# LED_1.net
KiCad netlist of a schematic drawn in Altium Designer
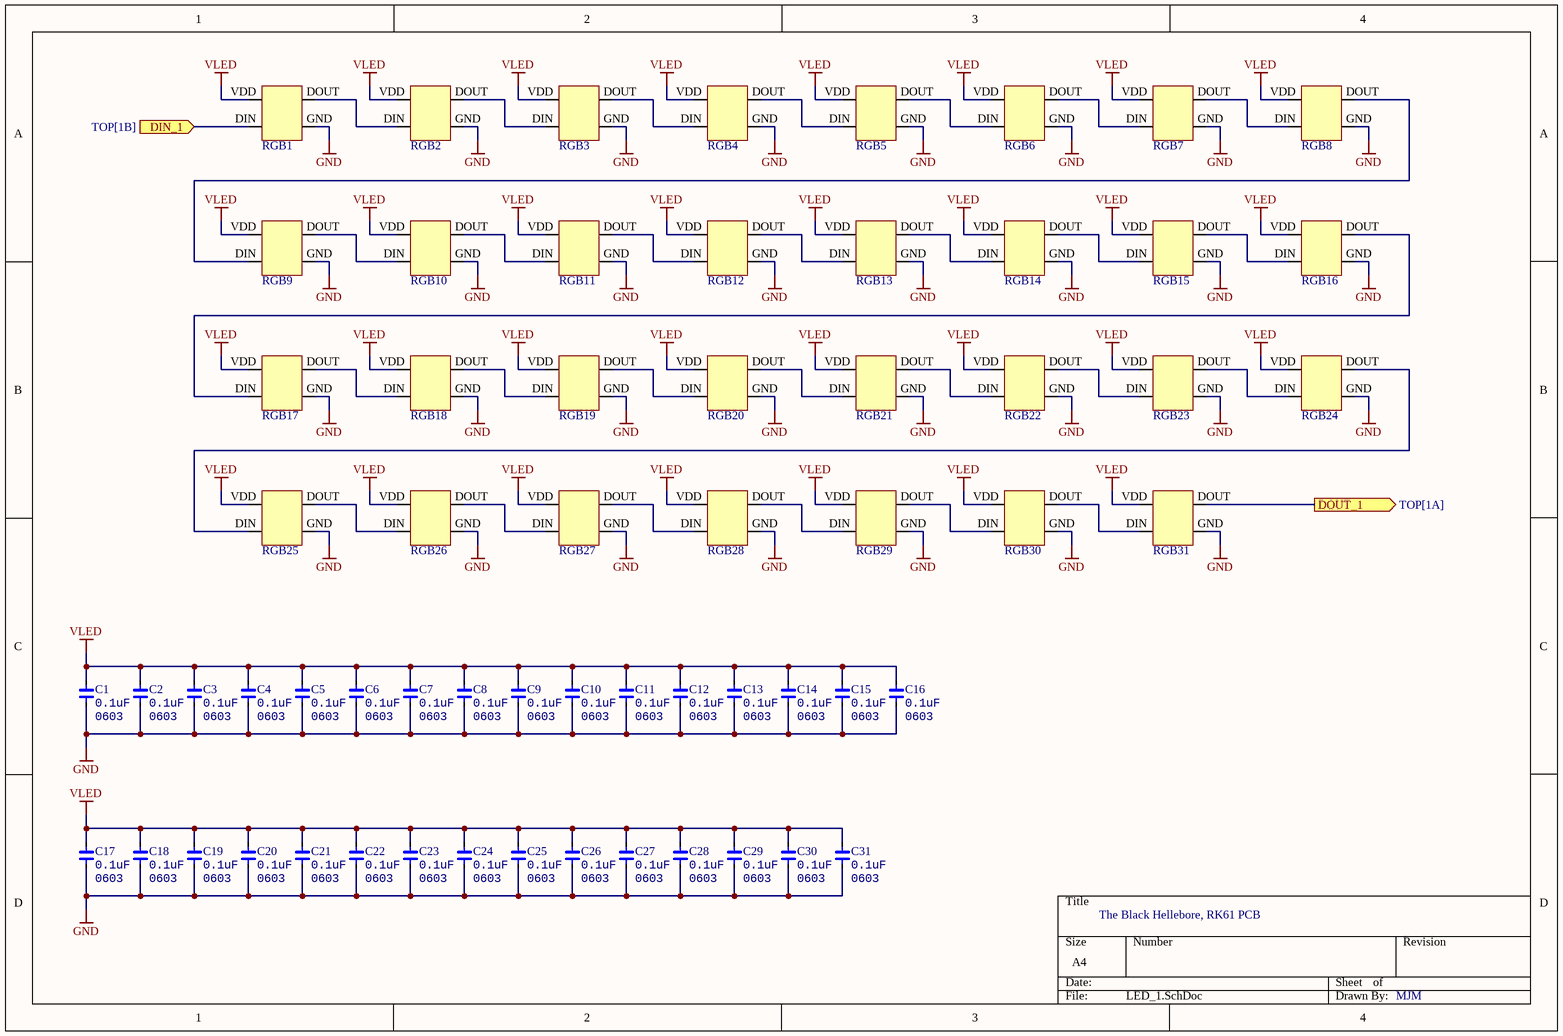
[diagram p0: LED_1.SchDoc]

(export (version "E")
  (design (tool "Eeschema 10.0.6"))
  (components
    (comp (ref "C1")
      (value "0.1uF")
      (footprint "FP-CC0603-DA-MFG")
      (description "0603 0.1 uF 50 V ±5 % Tolerance X7R SMT Multilayer Ceramic Capacitor")
      (fields (field (name "TYPE") "0603") (field (name "Comment") "CC0603JRX7R9BB104"))
      (libsource (lib "Microcom Corporation") (part "M_Cap"))
    )
    (comp (ref "C2")
      (value "0.1uF")
      (footprint "FP-CC0603-DA-MFG")
      (description "0603 0.1 uF 50 V ±5 % Tolerance X7R SMT Multilayer Ceramic Capacitor")
      (fields (field (name "TYPE") "0603") (field (name "Comment") "CC0603JRX7R9BB104"))
      (libsource (lib "Microcom Corporation") (part "M_Cap"))
    )
    (comp (ref "C3")
      (value "0.1uF")
      (footprint "FP-CC0603-DA-MFG")
      (description "0603 0.1 uF 50 V ±5 % Tolerance X7R SMT Multilayer Ceramic Capacitor")
      (fields (field (name "TYPE") "0603") (field (name "Comment") "CC0603JRX7R9BB104"))
      (libsource (lib "Microcom Corporation") (part "M_Cap"))
    )
    (comp (ref "C4")
      (value "0.1uF")
      (footprint "FP-CC0603-DA-MFG")
      (description "0603 0.1 uF 50 V ±5 % Tolerance X7R SMT Multilayer Ceramic Capacitor")
      (fields (field (name "TYPE") "0603") (field (name "Comment") "CC0603JRX7R9BB104"))
      (libsource (lib "Microcom Corporation") (part "M_Cap"))
    )
    (comp (ref "C5")
      (value "0.1uF")
      (footprint "FP-CC0603-DA-MFG")
      (description "0603 0.1 uF 50 V ±5 % Tolerance X7R SMT Multilayer Ceramic Capacitor")
      (fields (field (name "TYPE") "0603") (field (name "Comment") "CC0603JRX7R9BB104"))
      (libsource (lib "Microcom Corporation") (part "M_Cap"))
    )
    (comp (ref "C6")
      (value "0.1uF")
      (footprint "FP-CC0603-DA-MFG")
      (description "0603 0.1 uF 50 V ±5 % Tolerance X7R SMT Multilayer Ceramic Capacitor")
      (fields (field (name "TYPE") "0603") (field (name "Comment") "CC0603JRX7R9BB104"))
      (libsource (lib "Microcom Corporation") (part "M_Cap"))
    )
    (comp (ref "C7")
      (value "0.1uF")
      (footprint "FP-CC0603-DA-MFG")
      (description "0603 0.1 uF 50 V ±5 % Tolerance X7R SMT Multilayer Ceramic Capacitor")
      (fields (field (name "TYPE") "0603") (field (name "Comment") "CC0603JRX7R9BB104"))
      (libsource (lib "Microcom Corporation") (part "M_Cap"))
    )
    (comp (ref "C8")
      (value "0.1uF")
      (footprint "FP-CC0603-DA-MFG")
      (description "0603 0.1 uF 50 V ±5 % Tolerance X7R SMT Multilayer Ceramic Capacitor")
      (fields (field (name "TYPE") "0603") (field (name "Comment") "CC0603JRX7R9BB104"))
      (libsource (lib "Microcom Corporation") (part "M_Cap"))
    )
    (comp (ref "C9")
      (value "0.1uF")
      (footprint "FP-CC0603-DA-MFG")
      (description "0603 0.1 uF 50 V ±5 % Tolerance X7R SMT Multilayer Ceramic Capacitor")
      (fields (field (name "TYPE") "0603") (field (name "Comment") "CC0603JRX7R9BB104"))
      (libsource (lib "Microcom Corporation") (part "M_Cap"))
    )
    (comp (ref "C10")
      (value "0.1uF")
      (footprint "FP-CC0603-DA-MFG")
      (description "0603 0.1 uF 50 V ±5 % Tolerance X7R SMT Multilayer Ceramic Capacitor")
      (fields (field (name "TYPE") "0603") (field (name "Comment") "CC0603JRX7R9BB104"))
      (libsource (lib "Microcom Corporation") (part "M_Cap"))
    )
    (comp (ref "C11")
      (value "0.1uF")
      (footprint "FP-CC0603-DA-MFG")
      (description "0603 0.1 uF 50 V ±5 % Tolerance X7R SMT Multilayer Ceramic Capacitor")
      (fields (field (name "TYPE") "0603") (field (name "Comment") "CC0603JRX7R9BB104"))
      (libsource (lib "Microcom Corporation") (part "M_Cap"))
    )
    (comp (ref "C12")
      (value "0.1uF")
      (footprint "FP-CC0603-DA-MFG")
      (description "0603 0.1 uF 50 V ±5 % Tolerance X7R SMT Multilayer Ceramic Capacitor")
      (fields (field (name "TYPE") "0603") (field (name "Comment") "CC0603JRX7R9BB104"))
      (libsource (lib "Microcom Corporation") (part "M_Cap"))
    )
    (comp (ref "C13")
      (value "0.1uF")
      (footprint "FP-CC0603-DA-MFG")
      (description "0603 0.1 uF 50 V ±5 % Tolerance X7R SMT Multilayer Ceramic Capacitor")
      (fields (field (name "TYPE") "0603") (field (name "Comment") "CC0603JRX7R9BB104"))
      (libsource (lib "Microcom Corporation") (part "M_Cap"))
    )
    (comp (ref "C14")
      (value "0.1uF")
      (footprint "FP-CC0603-DA-MFG")
      (description "0603 0.1 uF 50 V ±5 % Tolerance X7R SMT Multilayer Ceramic Capacitor")
      (fields (field (name "TYPE") "0603") (field (name "Comment") "CC0603JRX7R9BB104"))
      (libsource (lib "Microcom Corporation") (part "M_Cap"))
    )
    (comp (ref "C15")
      (value "0.1uF")
      (footprint "FP-CC0603-DA-MFG")
      (description "0603 0.1 uF 50 V ±5 % Tolerance X7R SMT Multilayer Ceramic Capacitor")
      (fields (field (name "TYPE") "0603") (field (name "Comment") "CC0603JRX7R9BB104"))
      (libsource (lib "Microcom Corporation") (part "M_Cap"))
    )
    (comp (ref "C16")
      (value "0.1uF")
      (footprint "FP-CC0603-DA-MFG")
      (description "0603 0.1 uF 50 V ±5 % Tolerance X7R SMT Multilayer Ceramic Capacitor")
      (fields (field (name "TYPE") "0603") (field (name "Comment") "CC0603JRX7R9BB104"))
      (libsource (lib "Microcom Corporation") (part "M_Cap"))
    )
    (comp (ref "C17")
      (value "0.1uF")
      (footprint "FP-CC0603-DA-MFG")
      (description "0603 0.1 uF 50 V ±5 % Tolerance X7R SMT Multilayer Ceramic Capacitor")
      (fields (field (name "TYPE") "0603") (field (name "Comment") "CC0603JRX7R9BB104"))
      (libsource (lib "Microcom Corporation") (part "M_Cap"))
    )
    (comp (ref "C18")
      (value "0.1uF")
      (footprint "FP-CC0603-DA-MFG")
      (description "0603 0.1 uF 50 V ±5 % Tolerance X7R SMT Multilayer Ceramic Capacitor")
      (fields (field (name "TYPE") "0603") (field (name "Comment") "CC0603JRX7R9BB104"))
      (libsource (lib "Microcom Corporation") (part "M_Cap"))
    )
    (comp (ref "C19")
      (value "0.1uF")
      (footprint "FP-CC0603-DA-MFG")
      (description "0603 0.1 uF 50 V ±5 % Tolerance X7R SMT Multilayer Ceramic Capacitor")
      (fields (field (name "TYPE") "0603") (field (name "Comment") "CC0603JRX7R9BB104"))
      (libsource (lib "Microcom Corporation") (part "M_Cap"))
    )
    (comp (ref "C20")
      (value "0.1uF")
      (footprint "FP-CC0603-DA-MFG")
      (description "0603 0.1 uF 50 V ±5 % Tolerance X7R SMT Multilayer Ceramic Capacitor")
      (fields (field (name "TYPE") "0603") (field (name "Comment") "CC0603JRX7R9BB104"))
      (libsource (lib "Microcom Corporation") (part "M_Cap"))
    )
    (comp (ref "C21")
      (value "0.1uF")
      (footprint "FP-CC0603-DA-MFG")
      (description "0603 0.1 uF 50 V ±5 % Tolerance X7R SMT Multilayer Ceramic Capacitor")
      (fields (field (name "TYPE") "0603") (field (name "Comment") "CC0603JRX7R9BB104"))
      (libsource (lib "Microcom Corporation") (part "M_Cap"))
    )
    (comp (ref "C22")
      (value "0.1uF")
      (footprint "FP-CC0603-DA-MFG")
      (description "0603 0.1 uF 50 V ±5 % Tolerance X7R SMT Multilayer Ceramic Capacitor")
      (fields (field (name "TYPE") "0603") (field (name "Comment") "CC0603JRX7R9BB104"))
      (libsource (lib "Microcom Corporation") (part "M_Cap"))
    )
    (comp (ref "C23")
      (value "0.1uF")
      (footprint "FP-CC0603-DA-MFG")
      (description "0603 0.1 uF 50 V ±5 % Tolerance X7R SMT Multilayer Ceramic Capacitor")
      (fields (field (name "TYPE") "0603") (field (name "Comment") "CC0603JRX7R9BB104"))
      (libsource (lib "Microcom Corporation") (part "M_Cap"))
    )
    (comp (ref "C24")
      (value "0.1uF")
      (footprint "FP-CC0603-DA-MFG")
      (description "0603 0.1 uF 50 V ±5 % Tolerance X7R SMT Multilayer Ceramic Capacitor")
      (fields (field (name "TYPE") "0603") (field (name "Comment") "CC0603JRX7R9BB104"))
      (libsource (lib "Microcom Corporation") (part "M_Cap"))
    )
    (comp (ref "C25")
      (value "0.1uF")
      (footprint "FP-CC0603-DA-MFG")
      (description "0603 0.1 uF 50 V ±5 % Tolerance X7R SMT Multilayer Ceramic Capacitor")
      (fields (field (name "TYPE") "0603") (field (name "Comment") "CC0603JRX7R9BB104"))
      (libsource (lib "Microcom Corporation") (part "M_Cap"))
    )
    (comp (ref "C26")
      (value "0.1uF")
      (footprint "FP-CC0603-DA-MFG")
      (description "0603 0.1 uF 50 V ±5 % Tolerance X7R SMT Multilayer Ceramic Capacitor")
      (fields (field (name "TYPE") "0603") (field (name "Comment") "CC0603JRX7R9BB104"))
      (libsource (lib "Microcom Corporation") (part "M_Cap"))
    )
    (comp (ref "C27")
      (value "0.1uF")
      (footprint "FP-CC0603-DA-MFG")
      (description "0603 0.1 uF 50 V ±5 % Tolerance X7R SMT Multilayer Ceramic Capacitor")
      (fields (field (name "TYPE") "0603") (field (name "Comment") "CC0603JRX7R9BB104"))
      (libsource (lib "Microcom Corporation") (part "M_Cap"))
    )
    (comp (ref "C28")
      (value "0.1uF")
      (footprint "FP-CC0603-DA-MFG")
      (description "0603 0.1 uF 50 V ±5 % Tolerance X7R SMT Multilayer Ceramic Capacitor")
      (fields (field (name "TYPE") "0603") (field (name "Comment") "CC0603JRX7R9BB104"))
      (libsource (lib "Microcom Corporation") (part "M_Cap"))
    )
    (comp (ref "C29")
      (value "0.1uF")
      (footprint "FP-CC0603-DA-MFG")
      (description "0603 0.1 uF 50 V ±5 % Tolerance X7R SMT Multilayer Ceramic Capacitor")
      (fields (field (name "TYPE") "0603") (field (name "Comment") "CC0603JRX7R9BB104"))
      (libsource (lib "Microcom Corporation") (part "M_Cap"))
    )
    (comp (ref "C30")
      (value "0.1uF")
      (footprint "FP-CC0603-DA-MFG")
      (description "0603 0.1 uF 50 V ±5 % Tolerance X7R SMT Multilayer Ceramic Capacitor")
      (fields (field (name "TYPE") "0603") (field (name "Comment") "CC0603JRX7R9BB104"))
      (libsource (lib "Microcom Corporation") (part "M_Cap"))
    )
    (comp (ref "C31")
      (value "0.1uF")
      (footprint "FP-CC0603-DA-MFG")
      (description "0603 0.1 uF 50 V ±5 % Tolerance X7R SMT Multilayer Ceramic Capacitor")
      (fields (field (name "TYPE") "0603") (field (name "Comment") "CC0603JRX7R9BB104"))
      (libsource (lib "Microcom Corporation") (part "M_Cap"))
    )
    (comp (ref "RGB1")
      (value "SK6812MINI-E")
      (footprint "sk6812minie")
      (description "RGB LED SK6812MINI-E")
      (libsource (lib "Microcom Corporation") (part "SK6812MINI-E"))
    )
    (comp (ref "RGB2")
      (value "SK6812MINI-E")
      (footprint "sk6812minie")
      (description "RGB LED SK6812MINI-E")
      (libsource (lib "Microcom Corporation") (part "SK6812MINI-E"))
    )
    (comp (ref "RGB3")
      (value "SK6812MINI-E")
      (footprint "sk6812minie")
      (description "RGB LED SK6812MINI-E")
      (libsource (lib "Microcom Corporation") (part "SK6812MINI-E"))
    )
    (comp (ref "RGB4")
      (value "SK6812MINI-E")
      (footprint "sk6812minie")
      (description "RGB LED SK6812MINI-E")
      (libsource (lib "Microcom Corporation") (part "SK6812MINI-E"))
    )
    (comp (ref "RGB5")
      (value "SK6812MINI-E")
      (footprint "sk6812minie")
      (description "RGB LED SK6812MINI-E")
      (libsource (lib "Microcom Corporation") (part "SK6812MINI-E"))
    )
    (comp (ref "RGB6")
      (value "SK6812MINI-E")
      (footprint "sk6812minie")
      (description "RGB LED SK6812MINI-E")
      (libsource (lib "Microcom Corporation") (part "SK6812MINI-E"))
    )
    (comp (ref "RGB7")
      (value "SK6812MINI-E")
      (footprint "sk6812minie")
      (description "RGB LED SK6812MINI-E")
      (libsource (lib "Microcom Corporation") (part "SK6812MINI-E"))
    )
    (comp (ref "RGB8")
      (value "SK6812MINI-E")
      (footprint "sk6812minie")
      (description "RGB LED SK6812MINI-E")
      (libsource (lib "Microcom Corporation") (part "SK6812MINI-E"))
    )
    (comp (ref "RGB9")
      (value "SK6812MINI-E")
      (footprint "sk6812minie")
      (description "RGB LED SK6812MINI-E")
      (libsource (lib "Microcom Corporation") (part "SK6812MINI-E"))
    )
    (comp (ref "RGB10")
      (value "SK6812MINI-E")
      (footprint "sk6812minie")
      (description "RGB LED SK6812MINI-E")
      (libsource (lib "Microcom Corporation") (part "SK6812MINI-E"))
    )
    (comp (ref "RGB11")
      (value "SK6812MINI-E")
      (footprint "sk6812minie")
      (description "RGB LED SK6812MINI-E")
      (libsource (lib "Microcom Corporation") (part "SK6812MINI-E"))
    )
    (comp (ref "RGB12")
      (value "SK6812MINI-E")
      (footprint "sk6812minie")
      (description "RGB LED SK6812MINI-E")
      (libsource (lib "Microcom Corporation") (part "SK6812MINI-E"))
    )
    (comp (ref "RGB13")
      (value "SK6812MINI-E")
      (footprint "sk6812minie")
      (description "RGB LED SK6812MINI-E")
      (libsource (lib "Microcom Corporation") (part "SK6812MINI-E"))
    )
    (comp (ref "RGB14")
      (value "SK6812MINI-E")
      (footprint "sk6812minie")
      (description "RGB LED SK6812MINI-E")
      (libsource (lib "Microcom Corporation") (part "SK6812MINI-E"))
    )
    (comp (ref "RGB15")
      (value "SK6812MINI-E")
      (footprint "sk6812minie")
      (description "RGB LED SK6812MINI-E")
      (libsource (lib "Microcom Corporation") (part "SK6812MINI-E"))
    )
    (comp (ref "RGB16")
      (value "SK6812MINI-E")
      (footprint "sk6812minie")
      (description "RGB LED SK6812MINI-E")
      (libsource (lib "Microcom Corporation") (part "SK6812MINI-E"))
    )
    (comp (ref "RGB17")
      (value "SK6812MINI-E")
      (footprint "sk6812minie")
      (description "RGB LED SK6812MINI-E")
      (libsource (lib "Microcom Corporation") (part "SK6812MINI-E"))
    )
    (comp (ref "RGB18")
      (value "SK6812MINI-E")
      (footprint "sk6812minie")
      (description "RGB LED SK6812MINI-E")
      (libsource (lib "Microcom Corporation") (part "SK6812MINI-E"))
    )
    (comp (ref "RGB19")
      (value "SK6812MINI-E")
      (footprint "sk6812minie")
      (description "RGB LED SK6812MINI-E")
      (libsource (lib "Microcom Corporation") (part "SK6812MINI-E"))
    )
    (comp (ref "RGB20")
      (value "SK6812MINI-E")
      (footprint "sk6812minie")
      (description "RGB LED SK6812MINI-E")
      (libsource (lib "Microcom Corporation") (part "SK6812MINI-E"))
    )
    (comp (ref "RGB21")
      (value "SK6812MINI-E")
      (footprint "sk6812minie")
      (description "RGB LED SK6812MINI-E")
      (libsource (lib "Microcom Corporation") (part "SK6812MINI-E"))
    )
    (comp (ref "RGB22")
      (value "SK6812MINI-E")
      (footprint "sk6812minie")
      (description "RGB LED SK6812MINI-E")
      (libsource (lib "Microcom Corporation") (part "SK6812MINI-E"))
    )
    (comp (ref "RGB23")
      (value "SK6812MINI-E")
      (footprint "sk6812minie")
      (description "RGB LED SK6812MINI-E")
      (libsource (lib "Microcom Corporation") (part "SK6812MINI-E"))
    )
    (comp (ref "RGB24")
      (value "SK6812MINI-E")
      (footprint "sk6812minie")
      (description "RGB LED SK6812MINI-E")
      (libsource (lib "Microcom Corporation") (part "SK6812MINI-E"))
    )
    (comp (ref "RGB25")
      (value "SK6812MINI-E")
      (footprint "sk6812minie")
      (description "RGB LED SK6812MINI-E")
      (libsource (lib "Microcom Corporation") (part "SK6812MINI-E"))
    )
    (comp (ref "RGB26")
      (value "SK6812MINI-E")
      (footprint "sk6812minie")
      (description "RGB LED SK6812MINI-E")
      (libsource (lib "Microcom Corporation") (part "SK6812MINI-E"))
    )
    (comp (ref "RGB27")
      (value "SK6812MINI-E")
      (footprint "sk6812minie")
      (description "RGB LED SK6812MINI-E")
      (libsource (lib "Microcom Corporation") (part "SK6812MINI-E"))
    )
    (comp (ref "RGB28")
      (value "SK6812MINI-E")
      (footprint "sk6812minie")
      (description "RGB LED SK6812MINI-E")
      (libsource (lib "Microcom Corporation") (part "SK6812MINI-E"))
    )
    (comp (ref "RGB29")
      (value "SK6812MINI-E")
      (footprint "sk6812minie")
      (description "RGB LED SK6812MINI-E")
      (libsource (lib "Microcom Corporation") (part "SK6812MINI-E"))
    )
    (comp (ref "RGB30")
      (value "SK6812MINI-E")
      (footprint "sk6812minie")
      (description "RGB LED SK6812MINI-E")
      (libsource (lib "Microcom Corporation") (part "SK6812MINI-E"))
    )
    (comp (ref "RGB31")
      (value "SK6812MINI-E")
      (footprint "sk6812minie")
      (description "RGB LED SK6812MINI-E")
      (libsource (lib "Microcom Corporation") (part "SK6812MINI-E"))
    )
  )
  (nets
    (net (code "1") (name "/DIN_1") (class "Default")
      (node (ref "RGB1") (pin "DIN") (pinfunction "DIN_DIN") (pintype "passive"))
    )
    (net (code "2") (name "/DOUT_1") (class "Default")
      (node (ref "RGB31") (pin "DOUT") (pinfunction "DOUT_DOUT") (pintype "passive"))
    )
    (net (code "3") (name "GND") (class "Default")
      (node (ref "C1") (pin "1") (pinfunction "1_1") (pintype "passive"))
      (node (ref "C10") (pin "1") (pinfunction "1_1") (pintype "passive"))
      (node (ref "C11") (pin "1") (pinfunction "1_1") (pintype "passive"))
      (node (ref "C12") (pin "1") (pinfunction "1_1") (pintype "passive"))
      (node (ref "C13") (pin "1") (pinfunction "1_1") (pintype "passive"))
      (node (ref "C14") (pin "1") (pinfunction "1_1") (pintype "passive"))
      (node (ref "C15") (pin "1") (pinfunction "1_1") (pintype "passive"))
      (node (ref "C16") (pin "1") (pinfunction "1_1") (pintype "passive"))
      (node (ref "C17") (pin "1") (pinfunction "1_1") (pintype "passive"))
      (node (ref "C18") (pin "1") (pinfunction "1_1") (pintype "passive"))
      (node (ref "C19") (pin "1") (pinfunction "1_1") (pintype "passive"))
      (node (ref "C2") (pin "1") (pinfunction "1_1") (pintype "passive"))
      (node (ref "C20") (pin "1") (pinfunction "1_1") (pintype "passive"))
      (node (ref "C21") (pin "1") (pinfunction "1_1") (pintype "passive"))
      (node (ref "C22") (pin "1") (pinfunction "1_1") (pintype "passive"))
      (node (ref "C23") (pin "1") (pinfunction "1_1") (pintype "passive"))
      (node (ref "C24") (pin "1") (pinfunction "1_1") (pintype "passive"))
      (node (ref "C25") (pin "1") (pinfunction "1_1") (pintype "passive"))
      (node (ref "C26") (pin "1") (pinfunction "1_1") (pintype "passive"))
      (node (ref "C27") (pin "1") (pinfunction "1_1") (pintype "passive"))
      (node (ref "C28") (pin "1") (pinfunction "1_1") (pintype "passive"))
      (node (ref "C29") (pin "1") (pinfunction "1_1") (pintype "passive"))
      (node (ref "C3") (pin "1") (pinfunction "1_1") (pintype "passive"))
      (node (ref "C30") (pin "1") (pinfunction "1_1") (pintype "passive"))
      (node (ref "C31") (pin "1") (pinfunction "1_1") (pintype "passive"))
      (node (ref "C4") (pin "1") (pinfunction "1_1") (pintype "passive"))
      (node (ref "C5") (pin "1") (pinfunction "1_1") (pintype "passive"))
      (node (ref "C6") (pin "1") (pinfunction "1_1") (pintype "passive"))
      (node (ref "C7") (pin "1") (pinfunction "1_1") (pintype "passive"))
      (node (ref "C8") (pin "1") (pinfunction "1_1") (pintype "passive"))
      (node (ref "C9") (pin "1") (pinfunction "1_1") (pintype "passive"))
      (node (ref "RGB1") (pin "GND") (pinfunction "GND_GND") (pintype "passive"))
      (node (ref "RGB10") (pin "GND") (pinfunction "GND_GND") (pintype "passive"))
      (node (ref "RGB11") (pin "GND") (pinfunction "GND_GND") (pintype "passive"))
      (node (ref "RGB12") (pin "GND") (pinfunction "GND_GND") (pintype "passive"))
      (node (ref "RGB13") (pin "GND") (pinfunction "GND_GND") (pintype "passive"))
      (node (ref "RGB14") (pin "GND") (pinfunction "GND_GND") (pintype "passive"))
      (node (ref "RGB15") (pin "GND") (pinfunction "GND_GND") (pintype "passive"))
      (node (ref "RGB16") (pin "GND") (pinfunction "GND_GND") (pintype "passive"))
      (node (ref "RGB17") (pin "GND") (pinfunction "GND_GND") (pintype "passive"))
      (node (ref "RGB18") (pin "GND") (pinfunction "GND_GND") (pintype "passive"))
      (node (ref "RGB19") (pin "GND") (pinfunction "GND_GND") (pintype "passive"))
      (node (ref "RGB2") (pin "GND") (pinfunction "GND_GND") (pintype "passive"))
      (node (ref "RGB20") (pin "GND") (pinfunction "GND_GND") (pintype "passive"))
      (node (ref "RGB21") (pin "GND") (pinfunction "GND_GND") (pintype "passive"))
      (node (ref "RGB22") (pin "GND") (pinfunction "GND_GND") (pintype "passive"))
      (node (ref "RGB23") (pin "GND") (pinfunction "GND_GND") (pintype "passive"))
      (node (ref "RGB24") (pin "GND") (pinfunction "GND_GND") (pintype "passive"))
      (node (ref "RGB25") (pin "GND") (pinfunction "GND_GND") (pintype "passive"))
      (node (ref "RGB26") (pin "GND") (pinfunction "GND_GND") (pintype "passive"))
      (node (ref "RGB27") (pin "GND") (pinfunction "GND_GND") (pintype "passive"))
      (node (ref "RGB28") (pin "GND") (pinfunction "GND_GND") (pintype "passive"))
      (node (ref "RGB29") (pin "GND") (pinfunction "GND_GND") (pintype "passive"))
      (node (ref "RGB3") (pin "GND") (pinfunction "GND_GND") (pintype "passive"))
      (node (ref "RGB30") (pin "GND") (pinfunction "GND_GND") (pintype "passive"))
      (node (ref "RGB31") (pin "GND") (pinfunction "GND_GND") (pintype "passive"))
      (node (ref "RGB4") (pin "GND") (pinfunction "GND_GND") (pintype "passive"))
      (node (ref "RGB5") (pin "GND") (pinfunction "GND_GND") (pintype "passive"))
      (node (ref "RGB6") (pin "GND") (pinfunction "GND_GND") (pintype "passive"))
      (node (ref "RGB7") (pin "GND") (pinfunction "GND_GND") (pintype "passive"))
      (node (ref "RGB8") (pin "GND") (pinfunction "GND_GND") (pintype "passive"))
      (node (ref "RGB9") (pin "GND") (pinfunction "GND_GND") (pintype "passive"))
    )
    (net (code "4") (name "Net-(RGB1-PadDOUT)") (class "Default")
      (node (ref "RGB1") (pin "DOUT") (pinfunction "DOUT_DOUT") (pintype "passive"))
      (node (ref "RGB2") (pin "DIN") (pinfunction "DIN_DIN") (pintype "passive"))
    )
    (net (code "5") (name "Net-(RGB2-PadDOUT)") (class "Default")
      (node (ref "RGB2") (pin "DOUT") (pinfunction "DOUT_DOUT") (pintype "passive"))
      (node (ref "RGB3") (pin "DIN") (pinfunction "DIN_DIN") (pintype "passive"))
    )
    (net (code "6") (name "Net-(RGB3-PadDOUT)") (class "Default")
      (node (ref "RGB3") (pin "DOUT") (pinfunction "DOUT_DOUT") (pintype "passive"))
      (node (ref "RGB4") (pin "DIN") (pinfunction "DIN_DIN") (pintype "passive"))
    )
    (net (code "7") (name "Net-(RGB4-PadDOUT)") (class "Default")
      (node (ref "RGB4") (pin "DOUT") (pinfunction "DOUT_DOUT") (pintype "passive"))
      (node (ref "RGB5") (pin "DIN") (pinfunction "DIN_DIN") (pintype "passive"))
    )
    (net (code "8") (name "Net-(RGB5-PadDOUT)") (class "Default")
      (node (ref "RGB5") (pin "DOUT") (pinfunction "DOUT_DOUT") (pintype "passive"))
      (node (ref "RGB6") (pin "DIN") (pinfunction "DIN_DIN") (pintype "passive"))
    )
    (net (code "9") (name "Net-(RGB6-PadDOUT)") (class "Default")
      (node (ref "RGB6") (pin "DOUT") (pinfunction "DOUT_DOUT") (pintype "passive"))
      (node (ref "RGB7") (pin "DIN") (pinfunction "DIN_DIN") (pintype "passive"))
    )
    (net (code "10") (name "Net-(RGB7-PadDOUT)") (class "Default")
      (node (ref "RGB7") (pin "DOUT") (pinfunction "DOUT_DOUT") (pintype "passive"))
      (node (ref "RGB8") (pin "DIN") (pinfunction "DIN_DIN") (pintype "passive"))
    )
    (net (code "11") (name "Net-(RGB8-PadDOUT)") (class "Default")
      (node (ref "RGB8") (pin "DOUT") (pinfunction "DOUT_DOUT") (pintype "passive"))
      (node (ref "RGB9") (pin "DIN") (pinfunction "DIN_DIN") (pintype "passive"))
    )
    (net (code "12") (name "Net-(RGB10-PadDIN)") (class "Default")
      (node (ref "RGB10") (pin "DIN") (pinfunction "DIN_DIN") (pintype "passive"))
      (node (ref "RGB9") (pin "DOUT") (pinfunction "DOUT_DOUT") (pintype "passive"))
    )
    (net (code "13") (name "Net-(RGB10-PadDOUT)") (class "Default")
      (node (ref "RGB10") (pin "DOUT") (pinfunction "DOUT_DOUT") (pintype "passive"))
      (node (ref "RGB11") (pin "DIN") (pinfunction "DIN_DIN") (pintype "passive"))
    )
    (net (code "14") (name "Net-(RGB11-PadDOUT)") (class "Default")
      (node (ref "RGB11") (pin "DOUT") (pinfunction "DOUT_DOUT") (pintype "passive"))
      (node (ref "RGB12") (pin "DIN") (pinfunction "DIN_DIN") (pintype "passive"))
    )
    (net (code "15") (name "Net-(RGB12-PadDOUT)") (class "Default")
      (node (ref "RGB12") (pin "DOUT") (pinfunction "DOUT_DOUT") (pintype "passive"))
      (node (ref "RGB13") (pin "DIN") (pinfunction "DIN_DIN") (pintype "passive"))
    )
    (net (code "16") (name "Net-(RGB13-PadDOUT)") (class "Default")
      (node (ref "RGB13") (pin "DOUT") (pinfunction "DOUT_DOUT") (pintype "passive"))
      (node (ref "RGB14") (pin "DIN") (pinfunction "DIN_DIN") (pintype "passive"))
    )
    (net (code "17") (name "Net-(RGB14-PadDOUT)") (class "Default")
      (node (ref "RGB14") (pin "DOUT") (pinfunction "DOUT_DOUT") (pintype "passive"))
      (node (ref "RGB15") (pin "DIN") (pinfunction "DIN_DIN") (pintype "passive"))
    )
    (net (code "18") (name "Net-(RGB15-PadDOUT)") (class "Default")
      (node (ref "RGB15") (pin "DOUT") (pinfunction "DOUT_DOUT") (pintype "passive"))
      (node (ref "RGB16") (pin "DIN") (pinfunction "DIN_DIN") (pintype "passive"))
    )
    (net (code "19") (name "Net-(RGB16-PadDOUT)") (class "Default")
      (node (ref "RGB16") (pin "DOUT") (pinfunction "DOUT_DOUT") (pintype "passive"))
      (node (ref "RGB17") (pin "DIN") (pinfunction "DIN_DIN") (pintype "passive"))
    )
    (net (code "20") (name "Net-(RGB17-PadDOUT)") (class "Default")
      (node (ref "RGB17") (pin "DOUT") (pinfunction "DOUT_DOUT") (pintype "passive"))
      (node (ref "RGB18") (pin "DIN") (pinfunction "DIN_DIN") (pintype "passive"))
    )
    (net (code "21") (name "Net-(RGB18-PadDOUT)") (class "Default")
      (node (ref "RGB18") (pin "DOUT") (pinfunction "DOUT_DOUT") (pintype "passive"))
      (node (ref "RGB19") (pin "DIN") (pinfunction "DIN_DIN") (pintype "passive"))
    )
    (net (code "22") (name "Net-(RGB19-PadDOUT)") (class "Default")
      (node (ref "RGB19") (pin "DOUT") (pinfunction "DOUT_DOUT") (pintype "passive"))
      (node (ref "RGB20") (pin "DIN") (pinfunction "DIN_DIN") (pintype "passive"))
    )
    (net (code "23") (name "Net-(RGB20-PadDOUT)") (class "Default")
      (node (ref "RGB20") (pin "DOUT") (pinfunction "DOUT_DOUT") (pintype "passive"))
      (node (ref "RGB21") (pin "DIN") (pinfunction "DIN_DIN") (pintype "passive"))
    )
    (net (code "24") (name "Net-(RGB21-PadDOUT)") (class "Default")
      (node (ref "RGB21") (pin "DOUT") (pinfunction "DOUT_DOUT") (pintype "passive"))
      (node (ref "RGB22") (pin "DIN") (pinfunction "DIN_DIN") (pintype "passive"))
    )
    (net (code "25") (name "Net-(RGB22-PadDOUT)") (class "Default")
      (node (ref "RGB22") (pin "DOUT") (pinfunction "DOUT_DOUT") (pintype "passive"))
      (node (ref "RGB23") (pin "DIN") (pinfunction "DIN_DIN") (pintype "passive"))
    )
    (net (code "26") (name "Net-(RGB23-PadDOUT)") (class "Default")
      (node (ref "RGB23") (pin "DOUT") (pinfunction "DOUT_DOUT") (pintype "passive"))
      (node (ref "RGB24") (pin "DIN") (pinfunction "DIN_DIN") (pintype "passive"))
    )
    (net (code "27") (name "Net-(RGB24-PadDOUT)") (class "Default")
      (node (ref "RGB24") (pin "DOUT") (pinfunction "DOUT_DOUT") (pintype "passive"))
      (node (ref "RGB25") (pin "DIN") (pinfunction "DIN_DIN") (pintype "passive"))
    )
    (net (code "28") (name "Net-(RGB25-PadDOUT)") (class "Default")
      (node (ref "RGB25") (pin "DOUT") (pinfunction "DOUT_DOUT") (pintype "passive"))
      (node (ref "RGB26") (pin "DIN") (pinfunction "DIN_DIN") (pintype "passive"))
    )
    (net (code "29") (name "Net-(RGB26-PadDOUT)") (class "Default")
      (node (ref "RGB26") (pin "DOUT") (pinfunction "DOUT_DOUT") (pintype "passive"))
      (node (ref "RGB27") (pin "DIN") (pinfunction "DIN_DIN") (pintype "passive"))
    )
    (net (code "30") (name "Net-(RGB27-PadDOUT)") (class "Default")
      (node (ref "RGB27") (pin "DOUT") (pinfunction "DOUT_DOUT") (pintype "passive"))
      (node (ref "RGB28") (pin "DIN") (pinfunction "DIN_DIN") (pintype "passive"))
    )
    (net (code "31") (name "Net-(RGB28-PadDOUT)") (class "Default")
      (node (ref "RGB28") (pin "DOUT") (pinfunction "DOUT_DOUT") (pintype "passive"))
      (node (ref "RGB29") (pin "DIN") (pinfunction "DIN_DIN") (pintype "passive"))
    )
    (net (code "32") (name "Net-(RGB29-PadDOUT)") (class "Default")
      (node (ref "RGB29") (pin "DOUT") (pinfunction "DOUT_DOUT") (pintype "passive"))
      (node (ref "RGB30") (pin "DIN") (pinfunction "DIN_DIN") (pintype "passive"))
    )
    (net (code "33") (name "Net-(RGB30-PadDOUT)") (class "Default")
      (node (ref "RGB30") (pin "DOUT") (pinfunction "DOUT_DOUT") (pintype "passive"))
      (node (ref "RGB31") (pin "DIN") (pinfunction "DIN_DIN") (pintype "passive"))
    )
    (net (code "34") (name "VLED") (class "Default")
      (node (ref "C1") (pin "2") (pinfunction "2_2") (pintype "passive"))
      (node (ref "C10") (pin "2") (pinfunction "2_2") (pintype "passive"))
      (node (ref "C11") (pin "2") (pinfunction "2_2") (pintype "passive"))
      (node (ref "C12") (pin "2") (pinfunction "2_2") (pintype "passive"))
      (node (ref "C13") (pin "2") (pinfunction "2_2") (pintype "passive"))
      (node (ref "C14") (pin "2") (pinfunction "2_2") (pintype "passive"))
      (node (ref "C15") (pin "2") (pinfunction "2_2") (pintype "passive"))
      (node (ref "C16") (pin "2") (pinfunction "2_2") (pintype "passive"))
      (node (ref "C17") (pin "2") (pinfunction "2_2") (pintype "passive"))
      (node (ref "C18") (pin "2") (pinfunction "2_2") (pintype "passive"))
      (node (ref "C19") (pin "2") (pinfunction "2_2") (pintype "passive"))
      (node (ref "C2") (pin "2") (pinfunction "2_2") (pintype "passive"))
      (node (ref "C20") (pin "2") (pinfunction "2_2") (pintype "passive"))
      (node (ref "C21") (pin "2") (pinfunction "2_2") (pintype "passive"))
      (node (ref "C22") (pin "2") (pinfunction "2_2") (pintype "passive"))
      (node (ref "C23") (pin "2") (pinfunction "2_2") (pintype "passive"))
      (node (ref "C24") (pin "2") (pinfunction "2_2") (pintype "passive"))
      (node (ref "C25") (pin "2") (pinfunction "2_2") (pintype "passive"))
      (node (ref "C26") (pin "2") (pinfunction "2_2") (pintype "passive"))
      (node (ref "C27") (pin "2") (pinfunction "2_2") (pintype "passive"))
      (node (ref "C28") (pin "2") (pinfunction "2_2") (pintype "passive"))
      (node (ref "C29") (pin "2") (pinfunction "2_2") (pintype "passive"))
      (node (ref "C3") (pin "2") (pinfunction "2_2") (pintype "passive"))
      (node (ref "C30") (pin "2") (pinfunction "2_2") (pintype "passive"))
      (node (ref "C31") (pin "2") (pinfunction "2_2") (pintype "passive"))
      (node (ref "C4") (pin "2") (pinfunction "2_2") (pintype "passive"))
      (node (ref "C5") (pin "2") (pinfunction "2_2") (pintype "passive"))
      (node (ref "C6") (pin "2") (pinfunction "2_2") (pintype "passive"))
      (node (ref "C7") (pin "2") (pinfunction "2_2") (pintype "passive"))
      (node (ref "C8") (pin "2") (pinfunction "2_2") (pintype "passive"))
      (node (ref "C9") (pin "2") (pinfunction "2_2") (pintype "passive"))
      (node (ref "RGB1") (pin "VDD") (pinfunction "VDD_VDD") (pintype "passive"))
      (node (ref "RGB10") (pin "VDD") (pinfunction "VDD_VDD") (pintype "passive"))
      (node (ref "RGB11") (pin "VDD") (pinfunction "VDD_VDD") (pintype "passive"))
      (node (ref "RGB12") (pin "VDD") (pinfunction "VDD_VDD") (pintype "passive"))
      (node (ref "RGB13") (pin "VDD") (pinfunction "VDD_VDD") (pintype "passive"))
      (node (ref "RGB14") (pin "VDD") (pinfunction "VDD_VDD") (pintype "passive"))
      (node (ref "RGB15") (pin "VDD") (pinfunction "VDD_VDD") (pintype "passive"))
      (node (ref "RGB16") (pin "VDD") (pinfunction "VDD_VDD") (pintype "passive"))
      (node (ref "RGB17") (pin "VDD") (pinfunction "VDD_VDD") (pintype "passive"))
      (node (ref "RGB18") (pin "VDD") (pinfunction "VDD_VDD") (pintype "passive"))
      (node (ref "RGB19") (pin "VDD") (pinfunction "VDD_VDD") (pintype "passive"))
      (node (ref "RGB2") (pin "VDD") (pinfunction "VDD_VDD") (pintype "passive"))
      (node (ref "RGB20") (pin "VDD") (pinfunction "VDD_VDD") (pintype "passive"))
      (node (ref "RGB21") (pin "VDD") (pinfunction "VDD_VDD") (pintype "passive"))
      (node (ref "RGB22") (pin "VDD") (pinfunction "VDD_VDD") (pintype "passive"))
      (node (ref "RGB23") (pin "VDD") (pinfunction "VDD_VDD") (pintype "passive"))
      (node (ref "RGB24") (pin "VDD") (pinfunction "VDD_VDD") (pintype "passive"))
      (node (ref "RGB25") (pin "VDD") (pinfunction "VDD_VDD") (pintype "passive"))
      (node (ref "RGB26") (pin "VDD") (pinfunction "VDD_VDD") (pintype "passive"))
      (node (ref "RGB27") (pin "VDD") (pinfunction "VDD_VDD") (pintype "passive"))
      (node (ref "RGB28") (pin "VDD") (pinfunction "VDD_VDD") (pintype "passive"))
      (node (ref "RGB29") (pin "VDD") (pinfunction "VDD_VDD") (pintype "passive"))
      (node (ref "RGB3") (pin "VDD") (pinfunction "VDD_VDD") (pintype "passive"))
      (node (ref "RGB30") (pin "VDD") (pinfunction "VDD_VDD") (pintype "passive"))
      (node (ref "RGB31") (pin "VDD") (pinfunction "VDD_VDD") (pintype "passive"))
      (node (ref "RGB4") (pin "VDD") (pinfunction "VDD_VDD") (pintype "passive"))
      (node (ref "RGB5") (pin "VDD") (pinfunction "VDD_VDD") (pintype "passive"))
      (node (ref "RGB6") (pin "VDD") (pinfunction "VDD_VDD") (pintype "passive"))
      (node (ref "RGB7") (pin "VDD") (pinfunction "VDD_VDD") (pintype "passive"))
      (node (ref "RGB8") (pin "VDD") (pinfunction "VDD_VDD") (pintype "passive"))
      (node (ref "RGB9") (pin "VDD") (pinfunction "VDD_VDD") (pintype "passive"))
    )
  )
)
